# FTDI.net
KiCad netlist of a schematic drawn in Altium Designer
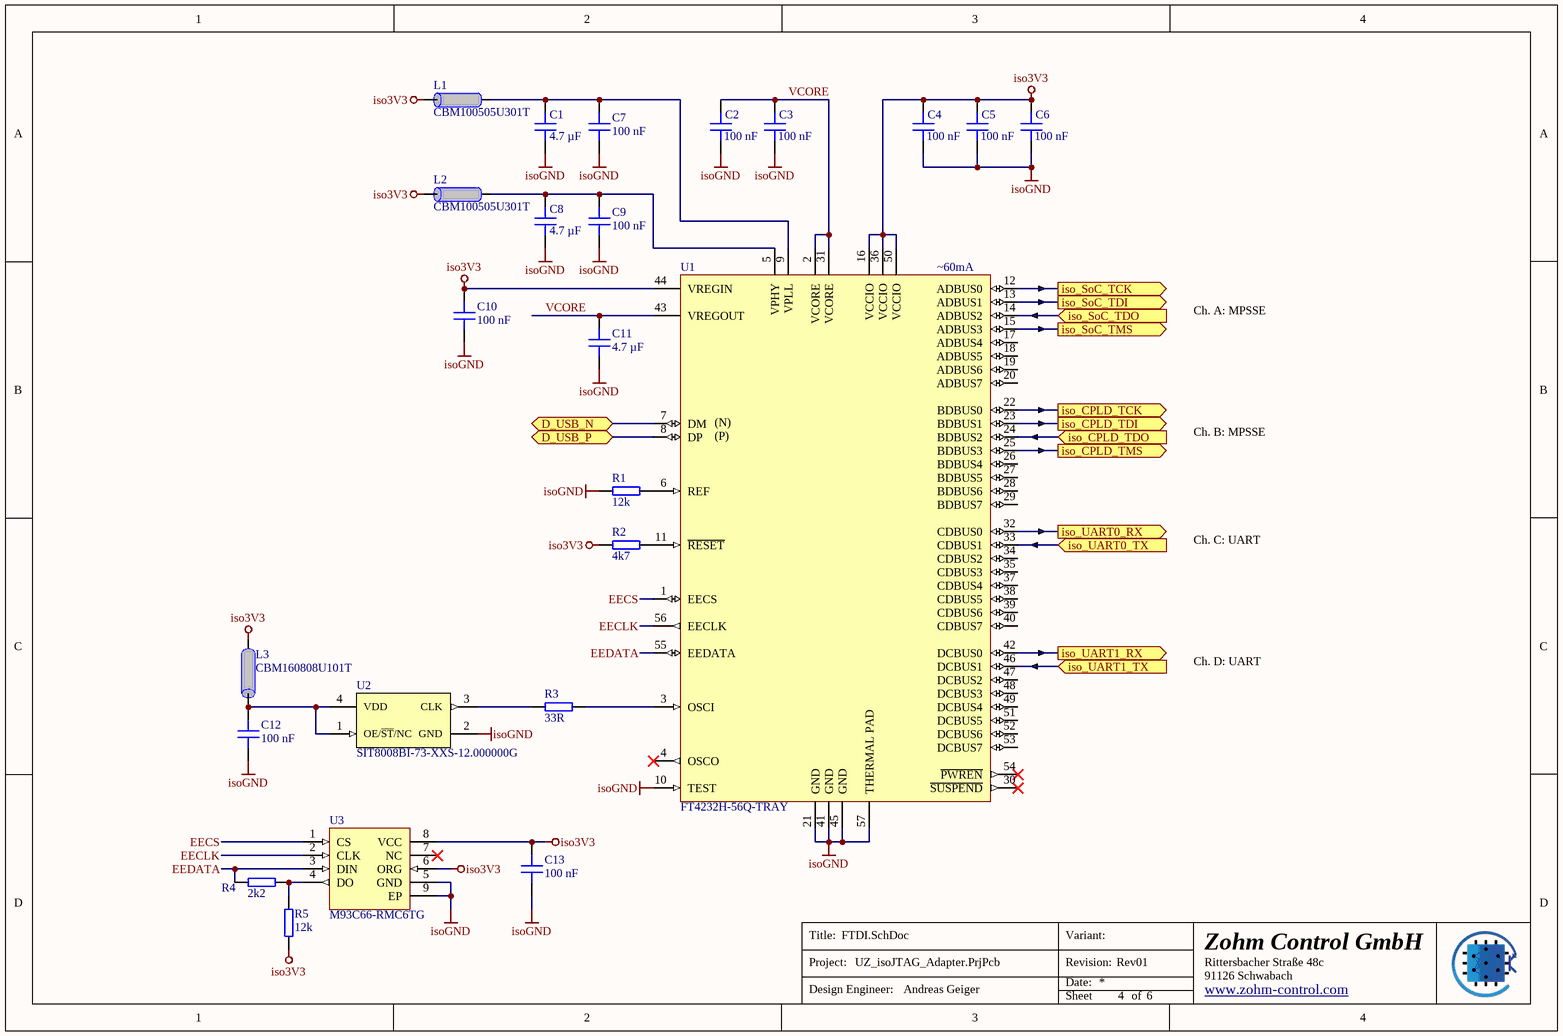
[diagram p0: FTDI.SchDoc]

(export (version "E")
  (design (tool "Eeschema 10.0.6"))
  (components
    (comp (ref "C1")
      (value "4.7 µF")
      (footprint "C_0402_TE")
      (description "6.3V 4.7uF X5R ±20% 0402 Multilayer Ceramic Capacitors MLCC - SMD/SMT ROHS")
      (fields
        (field (name "MANUFACTURER PART NUMBER") "CL05A475MQ5NRNC")
        (field (name "MANUFACTURER") "Samsung Electro-Mechanics")
        (field (name "CREATED FROM") "AGeiger")
      )
      (libsource (lib "user") (part "Capacitor"))
    )
    (comp (ref "C2")
      (value "100 nF")
      (footprint "C_0402_TE")
      (description "50V 100nF X7R ±10% 0402 Multilayer Ceramic Capacitors MLCC - SMD/SMT ROHS")
      (fields
        (field (name "MANUFACTURER PART NUMBER") "GRM155R71H104KE14D")
        (field (name "MANUFACTURER") "Murata Electronics")
        (field (name "CREATED FROM") "AGeiger")
      )
      (libsource (lib "user") (part "Capacitor"))
    )
    (comp (ref "C3")
      (value "100 nF")
      (footprint "C_0402_TE")
      (description "50V 100nF X7R ±10% 0402 Multilayer Ceramic Capacitors MLCC - SMD/SMT ROHS")
      (fields
        (field (name "MANUFACTURER PART NUMBER") "GRM155R71H104KE14D")
        (field (name "MANUFACTURER") "Murata Electronics")
        (field (name "CREATED FROM") "AGeiger")
      )
      (libsource (lib "user") (part "Capacitor"))
    )
    (comp (ref "C4")
      (value "100 nF")
      (footprint "C_0402_TE")
      (description "50V 100nF X7R ±10% 0402 Multilayer Ceramic Capacitors MLCC - SMD/SMT ROHS")
      (fields
        (field (name "MANUFACTURER PART NUMBER") "GRM155R71H104KE14D")
        (field (name "MANUFACTURER") "Murata Electronics")
        (field (name "CREATED FROM") "AGeiger")
      )
      (libsource (lib "user") (part "Capacitor"))
    )
    (comp (ref "C5")
      (value "100 nF")
      (footprint "C_0402_TE")
      (description "50V 100nF X7R ±10% 0402 Multilayer Ceramic Capacitors MLCC - SMD/SMT ROHS")
      (fields
        (field (name "MANUFACTURER PART NUMBER") "GRM155R71H104KE14D")
        (field (name "MANUFACTURER") "Murata Electronics")
        (field (name "CREATED FROM") "AGeiger")
      )
      (libsource (lib "user") (part "Capacitor"))
    )
    (comp (ref "C6")
      (value "100 nF")
      (footprint "C_0402_TE")
      (description "50V 100nF X7R ±10% 0402 Multilayer Ceramic Capacitors MLCC - SMD/SMT ROHS")
      (fields
        (field (name "MANUFACTURER PART NUMBER") "GRM155R71H104KE14D")
        (field (name "MANUFACTURER") "Murata Electronics")
        (field (name "CREATED FROM") "AGeiger")
      )
      (libsource (lib "user") (part "Capacitor"))
    )
    (comp (ref "C7")
      (value "100 nF")
      (footprint "C_0402_TE")
      (description "50V 100nF X7R ±10% 0402 Multilayer Ceramic Capacitors MLCC - SMD/SMT ROHS")
      (fields
        (field (name "MANUFACTURER PART NUMBER") "GRM155R71H104KE14D")
        (field (name "MANUFACTURER") "Murata Electronics")
        (field (name "CREATED FROM") "AGeiger")
      )
      (libsource (lib "user") (part "Capacitor"))
    )
    (comp (ref "C8")
      (value "4.7 µF")
      (footprint "C_0402_TE")
      (description "6.3V 4.7uF X5R ±20% 0402 Multilayer Ceramic Capacitors MLCC - SMD/SMT ROHS")
      (fields
        (field (name "MANUFACTURER PART NUMBER") "CL05A475MQ5NRNC")
        (field (name "MANUFACTURER") "Samsung Electro-Mechanics")
        (field (name "CREATED FROM") "AGeiger")
      )
      (libsource (lib "user") (part "Capacitor"))
    )
    (comp (ref "C9")
      (value "100 nF")
      (footprint "C_0402_TE")
      (description "50V 100nF X7R ±10% 0402 Multilayer Ceramic Capacitors MLCC - SMD/SMT ROHS")
      (fields
        (field (name "MANUFACTURER PART NUMBER") "GRM155R71H104KE14D")
        (field (name "MANUFACTURER") "Murata Electronics")
        (field (name "CREATED FROM") "AGeiger")
      )
      (libsource (lib "user") (part "Capacitor"))
    )
    (comp (ref "C10")
      (value "100 nF")
      (footprint "C_0402_TE")
      (description "50V 100nF X7R ±10% 0402 Multilayer Ceramic Capacitors MLCC - SMD/SMT ROHS")
      (fields
        (field (name "MANUFACTURER PART NUMBER") "GRM155R71H104KE14D")
        (field (name "MANUFACTURER") "Murata Electronics")
        (field (name "CREATED FROM") "AGeiger")
      )
      (libsource (lib "user") (part "Capacitor"))
    )
    (comp (ref "C11")
      (value "4.7 µF")
      (footprint "C_0402_TE")
      (description "6.3V 4.7uF X5R ±20% 0402 Multilayer Ceramic Capacitors MLCC - SMD/SMT ROHS")
      (fields
        (field (name "MANUFACTURER PART NUMBER") "CL05A475MQ5NRNC")
        (field (name "MANUFACTURER") "Samsung Electro-Mechanics")
        (field (name "CREATED FROM") "AGeiger")
      )
      (libsource (lib "user") (part "Capacitor"))
    )
    (comp (ref "C12")
      (value "100 nF")
      (footprint "C_0402_TE")
      (description "50V 100nF X7R ±10% 0402 Multilayer Ceramic Capacitors MLCC - SMD/SMT ROHS")
      (fields
        (field (name "MANUFACTURER PART NUMBER") "GRM155R71H104KE14D")
        (field (name "MANUFACTURER") "Murata Electronics")
        (field (name "CREATED FROM") "AGeiger")
      )
      (libsource (lib "user") (part "Capacitor"))
    )
    (comp (ref "C13")
      (value "100 nF")
      (footprint "C_0402_TE")
      (description "50V 100nF X7R ±10% 0402 Multilayer Ceramic Capacitors MLCC - SMD/SMT ROHS")
      (fields
        (field (name "MANUFACTURER PART NUMBER") "GRM155R71H104KE14D")
        (field (name "MANUFACTURER") "Murata Electronics")
        (field (name "CREATED FROM") "AGeiger")
      )
      (libsource (lib "user") (part "Capacitor"))
    )
    (comp (ref "L1")
      (value "CBM100505U301T")
      (footprint "IND_0402_TE")
      (description "300mΩ ±25% 300Ω@100MHz 0402 Ferrite Beads ROHS")
      (fields
        (field (name "MANUFACTURER") "FH (Guangdong Fenghua Advanced Tech)")
        (field (name "LCSC PART NUMBER") "C394406")
        (field (name "CREATED FROM") "AGeiger")
      )
      (libsource (lib "") (part "Ferrite_Bead_1"))
    )
    (comp (ref "L2")
      (value "CBM100505U301T")
      (footprint "IND_0402_TE")
      (description "300mΩ ±25% 300Ω@100MHz 0402 Ferrite Beads ROHS")
      (fields
        (field (name "MANUFACTURER") "FH (Guangdong Fenghua Advanced Tech)")
        (field (name "LCSC PART NUMBER") "C394406")
        (field (name "CREATED FROM") "AGeiger")
      )
      (libsource (lib "") (part "Ferrite_Bead_1"))
    )
    (comp (ref "L3")
      (value "CBM160808U101T")
      (footprint "IND_0603_TE")
      (description "60mΩ ±25% 100Ω@100MHz 0603 Ferrite Beads ROHS")
      (fields
        (field (name "MANUFACTURER") "FH (Guangdong Fenghua Advanced Tech)")
        (field (name "LCSC PART NUMBER") "C361675")
        (field (name "CREATED FROM") "AGeiger")
      )
      (libsource (lib "user") (part "Ferrite_Bead"))
    )
    (comp (ref "R1")
      (value "12k")
      (footprint "R_0402_TE")
      (description "62.5mW Thick Film Resistors ±100ppm/℃ ±1% 12kΩ 0402 Chip Resistor - Surface Mount ROHS")
      (fields
        (field (name "MANUFACTURER PART NUMBER") "RC0402FR-0712KL")
        (field (name "MANUFACTURER") "YAGEO")
        (field (name "CREATED FROM") "AGeiger")
      )
      (libsource (lib "user") (part "Resistor"))
    )
    (comp (ref "R2")
      (value "4k7")
      (footprint "R_0402_TE")
      (description "62.5mW Thick Film Resistors ±100ppm/℃ ±1% 4.7kΩ 0402 Chip Resistor - Surface Mount ROHS")
      (fields
        (field (name "MANUFACTURER PART NUMBER") "RC0402FR-074K7L")
        (field (name "MANUFACTURER") "YAGEO")
        (field (name "CREATED FROM") "AGeiger")
      )
      (libsource (lib "user") (part "Resistor"))
    )
    (comp (ref "R3")
      (value "33R")
      (footprint "R_0402_TE")
      (description "62.5mW Thick Film Resistors ±100ppm/℃ ±1% 33Ω 0402 Chip Resistor - Surface Mount ROHS")
      (fields
        (field (name "MANUFACTURER PART NUMBER") "RC0402FR-0733RL")
        (field (name "MANUFACTURER") "YAGEO")
        (field (name "CREATED FROM") "AGeiger")
      )
      (libsource (lib "user") (part "Resistor"))
    )
    (comp (ref "R4")
      (value "2k2")
      (footprint "R_0402_TE")
      (description "62.5mW Thick Film Resistors ±100ppm/℃ ±1% 2.2kΩ 0402 Chip Resistor - Surface Mount ROHS")
      (fields
        (field (name "MANUFACTURER PART NUMBER") "RC0402FR-072K2L")
        (field (name "MANUFACTURER") "YAGEO")
        (field (name "CREATED FROM") "AGeiger")
      )
      (libsource (lib "user") (part "Resistor"))
    )
    (comp (ref "R5")
      (value "12k")
      (footprint "R_0402_TE")
      (description "62.5mW Thick Film Resistors ±100ppm/℃ ±1% 12kΩ 0402 Chip Resistor - Surface Mount ROHS")
      (fields
        (field (name "MANUFACTURER PART NUMBER") "RC0402FR-0712KL")
        (field (name "MANUFACTURER") "YAGEO")
        (field (name "CREATED FROM") "AGeiger")
      )
      (libsource (lib "user") (part "Resistor"))
    )
    (comp (ref "U1")
      (value "FT4232H-56Q-TRAY")
      (footprint "QFN50P800X800-57T610X610N")
      (description "USB Interface IC Quad 480Mbs 4 UART USB 2.0 12Mbit")
      (fields
        (field (name "MANUFACTURER") "FTDI")
        (field (name "LCSC PART NUMBER") "C1521561")
        (field (name "CREATED FROM") "AGeiger")
      )
      (libsource (lib "user") (part "FT4232H-56Q"))
    )
    (comp (ref "U2")
      (value "SIT8008BI-73-XXS-12.000000G")
      (footprint "2016")
      (description "Clock-Standardoszillatoren -40 to 85C, 2016, 50ppm, 2.25V-3.63V, 12MHz, ST, 250 pcs T&R 8 mm")
      (fields
        (field (name "MANUFACTURER") "SiTime")
        (field (name "LCSC PART NUMBER") "C1508636")
        (field (name "CREATED FROM") "AGeiger")
      )
      (libsource (lib "user") (part "SiT8103"))
    )
    (comp (ref "U3")
      (value "M93C66-RMC6TG")
      (footprint "UFDFPN8")
      (description "4Kbit MICROWIRE EE 1.8 V to 5.5 V")
      (fields
        (field (name "MANUFACTURER") "STMicroelectronics")
        (field (name "LCSC PART NUMBER") "C2061956")
        (field (name "CREATED FROM") "AGeiger")
      )
      (libsource (lib "user") (part "M93C46-MN6P"))
    )
  )
  (nets
    (net (code "1") (name "/D_USB_N") (class "Default")
      (node (ref "U1") (pin "7") (pinfunction "DM_7") (pintype "bidirectional"))
    )
    (net (code "2") (name "/D_USB_P") (class "Default")
      (node (ref "U1") (pin "8") (pinfunction "DP_8") (pintype "bidirectional"))
    )
    (net (code "3") (name "/EECLK") (class "Default")
      (node (ref "U1") (pin "56") (pinfunction "EECLK_56") (pintype "output"))
      (node (ref "U3") (pin "2") (pinfunction "CLK_2") (pintype "input"))
    )
    (net (code "4") (name "/EECS") (class "Default")
      (node (ref "U1") (pin "1") (pinfunction "EECS_1") (pintype "bidirectional"))
      (node (ref "U3") (pin "1") (pinfunction "CS_1") (pintype "input"))
    )
    (net (code "5") (name "/EEDATA") (class "Default")
      (node (ref "R4") (pin "1") (pinfunction "1_1") (pintype "passive"))
      (node (ref "U1") (pin "55") (pinfunction "EEDATA_55") (pintype "bidirectional"))
      (node (ref "U3") (pin "3") (pinfunction "DIN_3") (pintype "input"))
    )
    (net (code "6") (name "/VCORE") (class "Default")
      (node (ref "C11") (pin "2") (pinfunction "2_2") (pintype "passive"))
      (node (ref "C2") (pin "2") (pinfunction "2_2") (pintype "passive"))
      (node (ref "C3") (pin "2") (pinfunction "2_2") (pintype "passive"))
      (node (ref "U1") (pin "2") (pinfunction "VCORE_2") (pintype "power_in"))
      (node (ref "U1") (pin "31") (pinfunction "VCORE_31") (pintype "power_in"))
      (node (ref "U1") (pin "43") (pinfunction "VREGOUT_43") (pintype "power_in"))
    )
    (net (code "7") (name "/iso_CPLD_TCK") (class "Default")
      (node (ref "U1") (pin "22") (pinfunction "BDBUS0_22") (pintype "bidirectional"))
    )
    (net (code "8") (name "/iso_CPLD_TDI") (class "Default")
      (node (ref "U1") (pin "23") (pinfunction "BDBUS1_23") (pintype "bidirectional"))
    )
    (net (code "9") (name "/iso_CPLD_TDO") (class "Default")
      (node (ref "U1") (pin "24") (pinfunction "BDBUS2_24") (pintype "bidirectional"))
    )
    (net (code "10") (name "/iso_CPLD_TMS") (class "Default")
      (node (ref "U1") (pin "25") (pinfunction "BDBUS3_25") (pintype "bidirectional"))
    )
    (net (code "11") (name "/iso_SoC_TCK") (class "Default")
      (node (ref "U1") (pin "12") (pinfunction "ADBUS0_12") (pintype "bidirectional"))
    )
    (net (code "12") (name "/iso_SoC_TDI") (class "Default")
      (node (ref "U1") (pin "13") (pinfunction "ADBUS1_13") (pintype "bidirectional"))
    )
    (net (code "13") (name "/iso_SoC_TDO") (class "Default")
      (node (ref "U1") (pin "14") (pinfunction "ADBUS2_14") (pintype "bidirectional"))
    )
    (net (code "14") (name "/iso_SoC_TMS") (class "Default")
      (node (ref "U1") (pin "15") (pinfunction "ADBUS3_15") (pintype "bidirectional"))
    )
    (net (code "15") (name "/iso_UART0_RX") (class "Default")
      (node (ref "U1") (pin "32") (pinfunction "CDBUS0_32") (pintype "bidirectional"))
    )
    (net (code "16") (name "/iso_UART0_TX") (class "Default")
      (node (ref "U1") (pin "33") (pinfunction "CDBUS1_33") (pintype "bidirectional"))
    )
    (net (code "17") (name "/iso_UART1_RX") (class "Default")
      (node (ref "U1") (pin "42") (pinfunction "DCBUS0_42") (pintype "bidirectional"))
    )
    (net (code "18") (name "/iso_UART1_TX") (class "Default")
      (node (ref "U1") (pin "46") (pinfunction "DCBUS1_46") (pintype "bidirectional"))
    )
    (net (code "19") (name "Net-(U1-OSCI)") (class "Default")
      (node (ref "R3") (pin "2") (pinfunction "2_2") (pintype "passive"))
      (node (ref "U1") (pin "3") (pinfunction "OSCI_3") (pintype "input"))
    )
    (net (code "20") (name "Net-(U1-REF)") (class "Default")
      (node (ref "R1") (pin "2") (pinfunction "2_2") (pintype "passive"))
      (node (ref "U1") (pin "6") (pinfunction "REF_6") (pintype "input"))
    )
    (net (code "21") (name "Net-(U1-VPHY)") (class "Default")
      (node (ref "C8") (pin "2") (pinfunction "2_2") (pintype "passive"))
      (node (ref "C9") (pin "2") (pinfunction "2_2") (pintype "passive"))
      (node (ref "L2") (pin "1") (pinfunction "1_1") (pintype "passive"))
      (node (ref "U1") (pin "5") (pinfunction "VPHY_5") (pintype "power_in"))
    )
    (net (code "22") (name "Net-(U1-VPLL)") (class "Default")
      (node (ref "C1") (pin "2") (pinfunction "2_2") (pintype "passive"))
      (node (ref "C7") (pin "2") (pinfunction "2_2") (pintype "passive"))
      (node (ref "L1") (pin "1") (pinfunction "1_1") (pintype "passive"))
      (node (ref "U1") (pin "9") (pinfunction "VPLL_9") (pintype "power_in"))
    )
    (net (code "23") (name "Net-(U1-~{RESET})") (class "Default")
      (node (ref "R2") (pin "2") (pinfunction "2_2") (pintype "passive"))
      (node (ref "U1") (pin "11") (pinfunction "~{RESET}_11") (pintype "input"))
    )
    (net (code "24") (name "Net-(U2-CLK)") (class "Default")
      (node (ref "R3") (pin "1") (pinfunction "1_1") (pintype "passive"))
      (node (ref "U2") (pin "3") (pinfunction "CLK_3") (pintype "output"))
    )
    (net (code "25") (name "Net-(U2-OE{slash}~{ST}{slash}NC)") (class "Default")
      (node (ref "C12") (pin "2") (pinfunction "2_2") (pintype "passive"))
      (node (ref "L3") (pin "2") (pinfunction "2_2") (pintype "passive"))
      (node (ref "U2") (pin "1") (pinfunction "OE/~{ST}/NC_1") (pintype "input"))
      (node (ref "U2") (pin "4") (pinfunction "VDD_4") (pintype "power_in"))
    )
    (net (code "26") (name "Net-(U3-DO)") (class "Default")
      (node (ref "R4") (pin "2") (pinfunction "2_2") (pintype "passive"))
      (node (ref "R5") (pin "2") (pinfunction "2_2") (pintype "passive"))
      (node (ref "U3") (pin "4") (pinfunction "DO_4") (pintype "output"))
    )
    (net (code "27") (name "iso3V3") (class "Default")
      (node (ref "C10") (pin "2") (pinfunction "2_2") (pintype "passive"))
      (node (ref "C13") (pin "2") (pinfunction "2_2") (pintype "passive"))
      (node (ref "C4") (pin "2") (pinfunction "2_2") (pintype "passive"))
      (node (ref "C5") (pin "2") (pinfunction "2_2") (pintype "passive"))
      (node (ref "C6") (pin "2") (pinfunction "2_2") (pintype "passive"))
      (node (ref "L1") (pin "2") (pinfunction "2_2") (pintype "passive"))
      (node (ref "L2") (pin "2") (pinfunction "2_2") (pintype "passive"))
      (node (ref "L3") (pin "1") (pinfunction "1_1") (pintype "passive"))
      (node (ref "R2") (pin "1") (pinfunction "1_1") (pintype "passive"))
      (node (ref "R5") (pin "1") (pinfunction "1_1") (pintype "passive"))
      (node (ref "U1") (pin "16") (pinfunction "VCCIO_16") (pintype "power_in"))
      (node (ref "U1") (pin "36") (pinfunction "VCCIO_36") (pintype "power_in"))
      (node (ref "U1") (pin "44") (pinfunction "VREGIN_44") (pintype "power_in"))
      (node (ref "U1") (pin "50") (pinfunction "VCCIO_50") (pintype "power_in"))
      (node (ref "U3") (pin "6") (pinfunction "ORG_6") (pintype "input"))
      (node (ref "U3") (pin "8") (pinfunction "VCC_8") (pintype "power_in"))
    )
    (net (code "28") (name "isoGND") (class "Default")
      (node (ref "C1") (pin "1") (pinfunction "1_1") (pintype "passive"))
      (node (ref "C10") (pin "1") (pinfunction "1_1") (pintype "passive"))
      (node (ref "C11") (pin "1") (pinfunction "1_1") (pintype "passive"))
      (node (ref "C12") (pin "1") (pinfunction "1_1") (pintype "passive"))
      (node (ref "C13") (pin "1") (pinfunction "1_1") (pintype "passive"))
      (node (ref "C2") (pin "1") (pinfunction "1_1") (pintype "passive"))
      (node (ref "C3") (pin "1") (pinfunction "1_1") (pintype "passive"))
      (node (ref "C4") (pin "1") (pinfunction "1_1") (pintype "passive"))
      (node (ref "C5") (pin "1") (pinfunction "1_1") (pintype "passive"))
      (node (ref "C6") (pin "1") (pinfunction "1_1") (pintype "passive"))
      (node (ref "C7") (pin "1") (pinfunction "1_1") (pintype "passive"))
      (node (ref "C8") (pin "1") (pinfunction "1_1") (pintype "passive"))
      (node (ref "C9") (pin "1") (pinfunction "1_1") (pintype "passive"))
      (node (ref "R1") (pin "1") (pinfunction "1_1") (pintype "passive"))
      (node (ref "U1") (pin "10") (pinfunction "TEST_10") (pintype "input"))
      (node (ref "U1") (pin "21") (pinfunction "GND_21") (pintype "power_in"))
      (node (ref "U1") (pin "41") (pinfunction "GND_41") (pintype "power_in"))
      (node (ref "U1") (pin "45") (pinfunction "GND_45") (pintype "power_in"))
      (node (ref "U1") (pin "57") (pinfunction "THERMAL_PAD_57") (pintype "power_in"))
      (node (ref "U2") (pin "2") (pinfunction "GND_2") (pintype "power_in"))
      (node (ref "U3") (pin "5") (pinfunction "GND_5") (pintype "power_in"))
      (node (ref "U3") (pin "9") (pinfunction "EP_9") (pintype "power_in"))
    )
    (net (code "29") (name "unconnected-(U1-ADBUS4-Pad17)") (class "Default")
      (node (ref "U1") (pin "17") (pinfunction "ADBUS4_17") (pintype "bidirectional"))
    )
    (net (code "30") (name "unconnected-(U1-ADBUS5-Pad18)") (class "Default")
      (node (ref "U1") (pin "18") (pinfunction "ADBUS5_18") (pintype "bidirectional"))
    )
    (net (code "31") (name "unconnected-(U1-ADBUS6-Pad19)") (class "Default")
      (node (ref "U1") (pin "19") (pinfunction "ADBUS6_19") (pintype "bidirectional"))
    )
    (net (code "32") (name "unconnected-(U1-ADBUS7-Pad20)") (class "Default")
      (node (ref "U1") (pin "20") (pinfunction "ADBUS7_20") (pintype "bidirectional"))
    )
    (net (code "33") (name "unconnected-(U1-BDBUS4-Pad26)") (class "Default")
      (node (ref "U1") (pin "26") (pinfunction "BDBUS4_26") (pintype "bidirectional"))
    )
    (net (code "34") (name "unconnected-(U1-BDBUS5-Pad27)") (class "Default")
      (node (ref "U1") (pin "27") (pinfunction "BDBUS5_27") (pintype "bidirectional"))
    )
    (net (code "35") (name "unconnected-(U1-BDBUS6-Pad28)") (class "Default")
      (node (ref "U1") (pin "28") (pinfunction "BDBUS6_28") (pintype "bidirectional"))
    )
    (net (code "36") (name "unconnected-(U1-BDBUS7-Pad29)") (class "Default")
      (node (ref "U1") (pin "29") (pinfunction "BDBUS7_29") (pintype "bidirectional"))
    )
    (net (code "37") (name "unconnected-(U1-CDBUS2-Pad34)") (class "Default")
      (node (ref "U1") (pin "34") (pinfunction "CDBUS2_34") (pintype "bidirectional"))
    )
    (net (code "38") (name "unconnected-(U1-CDBUS3-Pad35)") (class "Default")
      (node (ref "U1") (pin "35") (pinfunction "CDBUS3_35") (pintype "bidirectional"))
    )
    (net (code "39") (name "unconnected-(U1-CDBUS4-Pad37)") (class "Default")
      (node (ref "U1") (pin "37") (pinfunction "CDBUS4_37") (pintype "bidirectional"))
    )
    (net (code "40") (name "unconnected-(U1-CDBUS5-Pad38)") (class "Default")
      (node (ref "U1") (pin "38") (pinfunction "CDBUS5_38") (pintype "bidirectional"))
    )
    (net (code "41") (name "unconnected-(U1-CDBUS6-Pad39)") (class "Default")
      (node (ref "U1") (pin "39") (pinfunction "CDBUS6_39") (pintype "bidirectional"))
    )
    (net (code "42") (name "unconnected-(U1-CDBUS7-Pad40)") (class "Default")
      (node (ref "U1") (pin "40") (pinfunction "CDBUS7_40") (pintype "bidirectional"))
    )
    (net (code "43") (name "unconnected-(U1-DCBUS2-Pad47)") (class "Default")
      (node (ref "U1") (pin "47") (pinfunction "DCBUS2_47") (pintype "bidirectional"))
    )
    (net (code "44") (name "unconnected-(U1-DCBUS3-Pad48)") (class "Default")
      (node (ref "U1") (pin "48") (pinfunction "DCBUS3_48") (pintype "bidirectional"))
    )
    (net (code "45") (name "unconnected-(U1-DCBUS4-Pad49)") (class "Default")
      (node (ref "U1") (pin "49") (pinfunction "DCBUS4_49") (pintype "bidirectional"))
    )
    (net (code "46") (name "unconnected-(U1-DCBUS5-Pad51)") (class "Default")
      (node (ref "U1") (pin "51") (pinfunction "DCBUS5_51") (pintype "bidirectional"))
    )
    (net (code "47") (name "unconnected-(U1-DCBUS6-Pad52)") (class "Default")
      (node (ref "U1") (pin "52") (pinfunction "DCBUS6_52") (pintype "bidirectional"))
    )
    (net (code "48") (name "unconnected-(U1-DCBUS7-Pad53)") (class "Default")
      (node (ref "U1") (pin "53") (pinfunction "DCBUS7_53") (pintype "bidirectional"))
    )
    (net (code "49") (name "unconnected-(U1-OSCO-Pad4)") (class "Default")
      (node (ref "U1") (pin "4") (pinfunction "OSCO_4") (pintype "output+no_connect"))
    )
    (net (code "50") (name "unconnected-(U1-~{PWREN}-Pad54)") (class "Default")
      (node (ref "U1") (pin "54") (pinfunction "~{PWREN}_54") (pintype "output+no_connect"))
    )
    (net (code "51") (name "unconnected-(U1-~{SUSPEND}-Pad30)") (class "Default")
      (node (ref "U1") (pin "30") (pinfunction "~{SUSPEND}_30") (pintype "output+no_connect"))
    )
    (net (code "52") (name "unconnected-(U3-NC-Pad7)") (class "Default")
      (node (ref "U3") (pin "7") (pinfunction "NC_7") (pintype "passive+no_connect"))
    )
  )
)
